# dynavo-amp.net
KiCad netlist of a schematic drawn in EAGLE
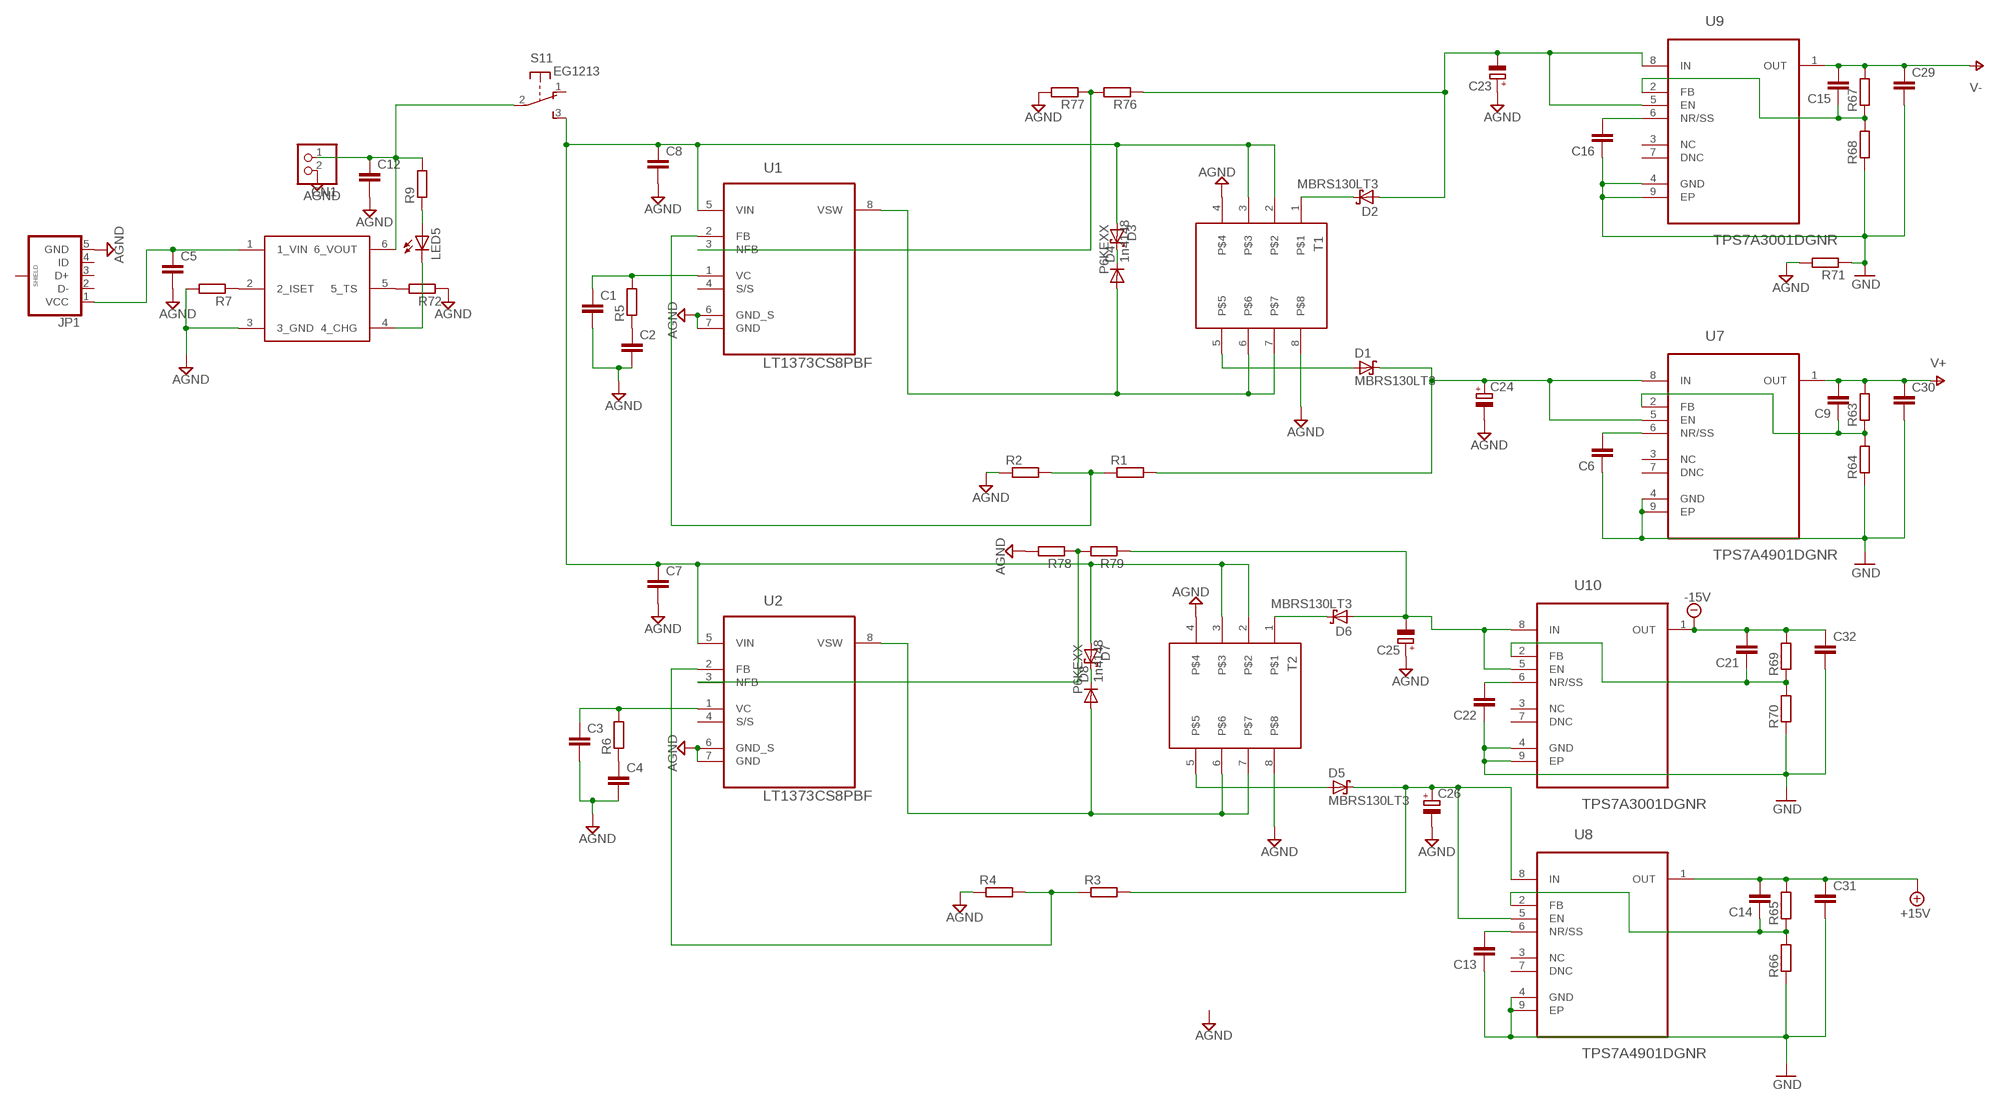
[diagram p0: schematic, sheet 1]
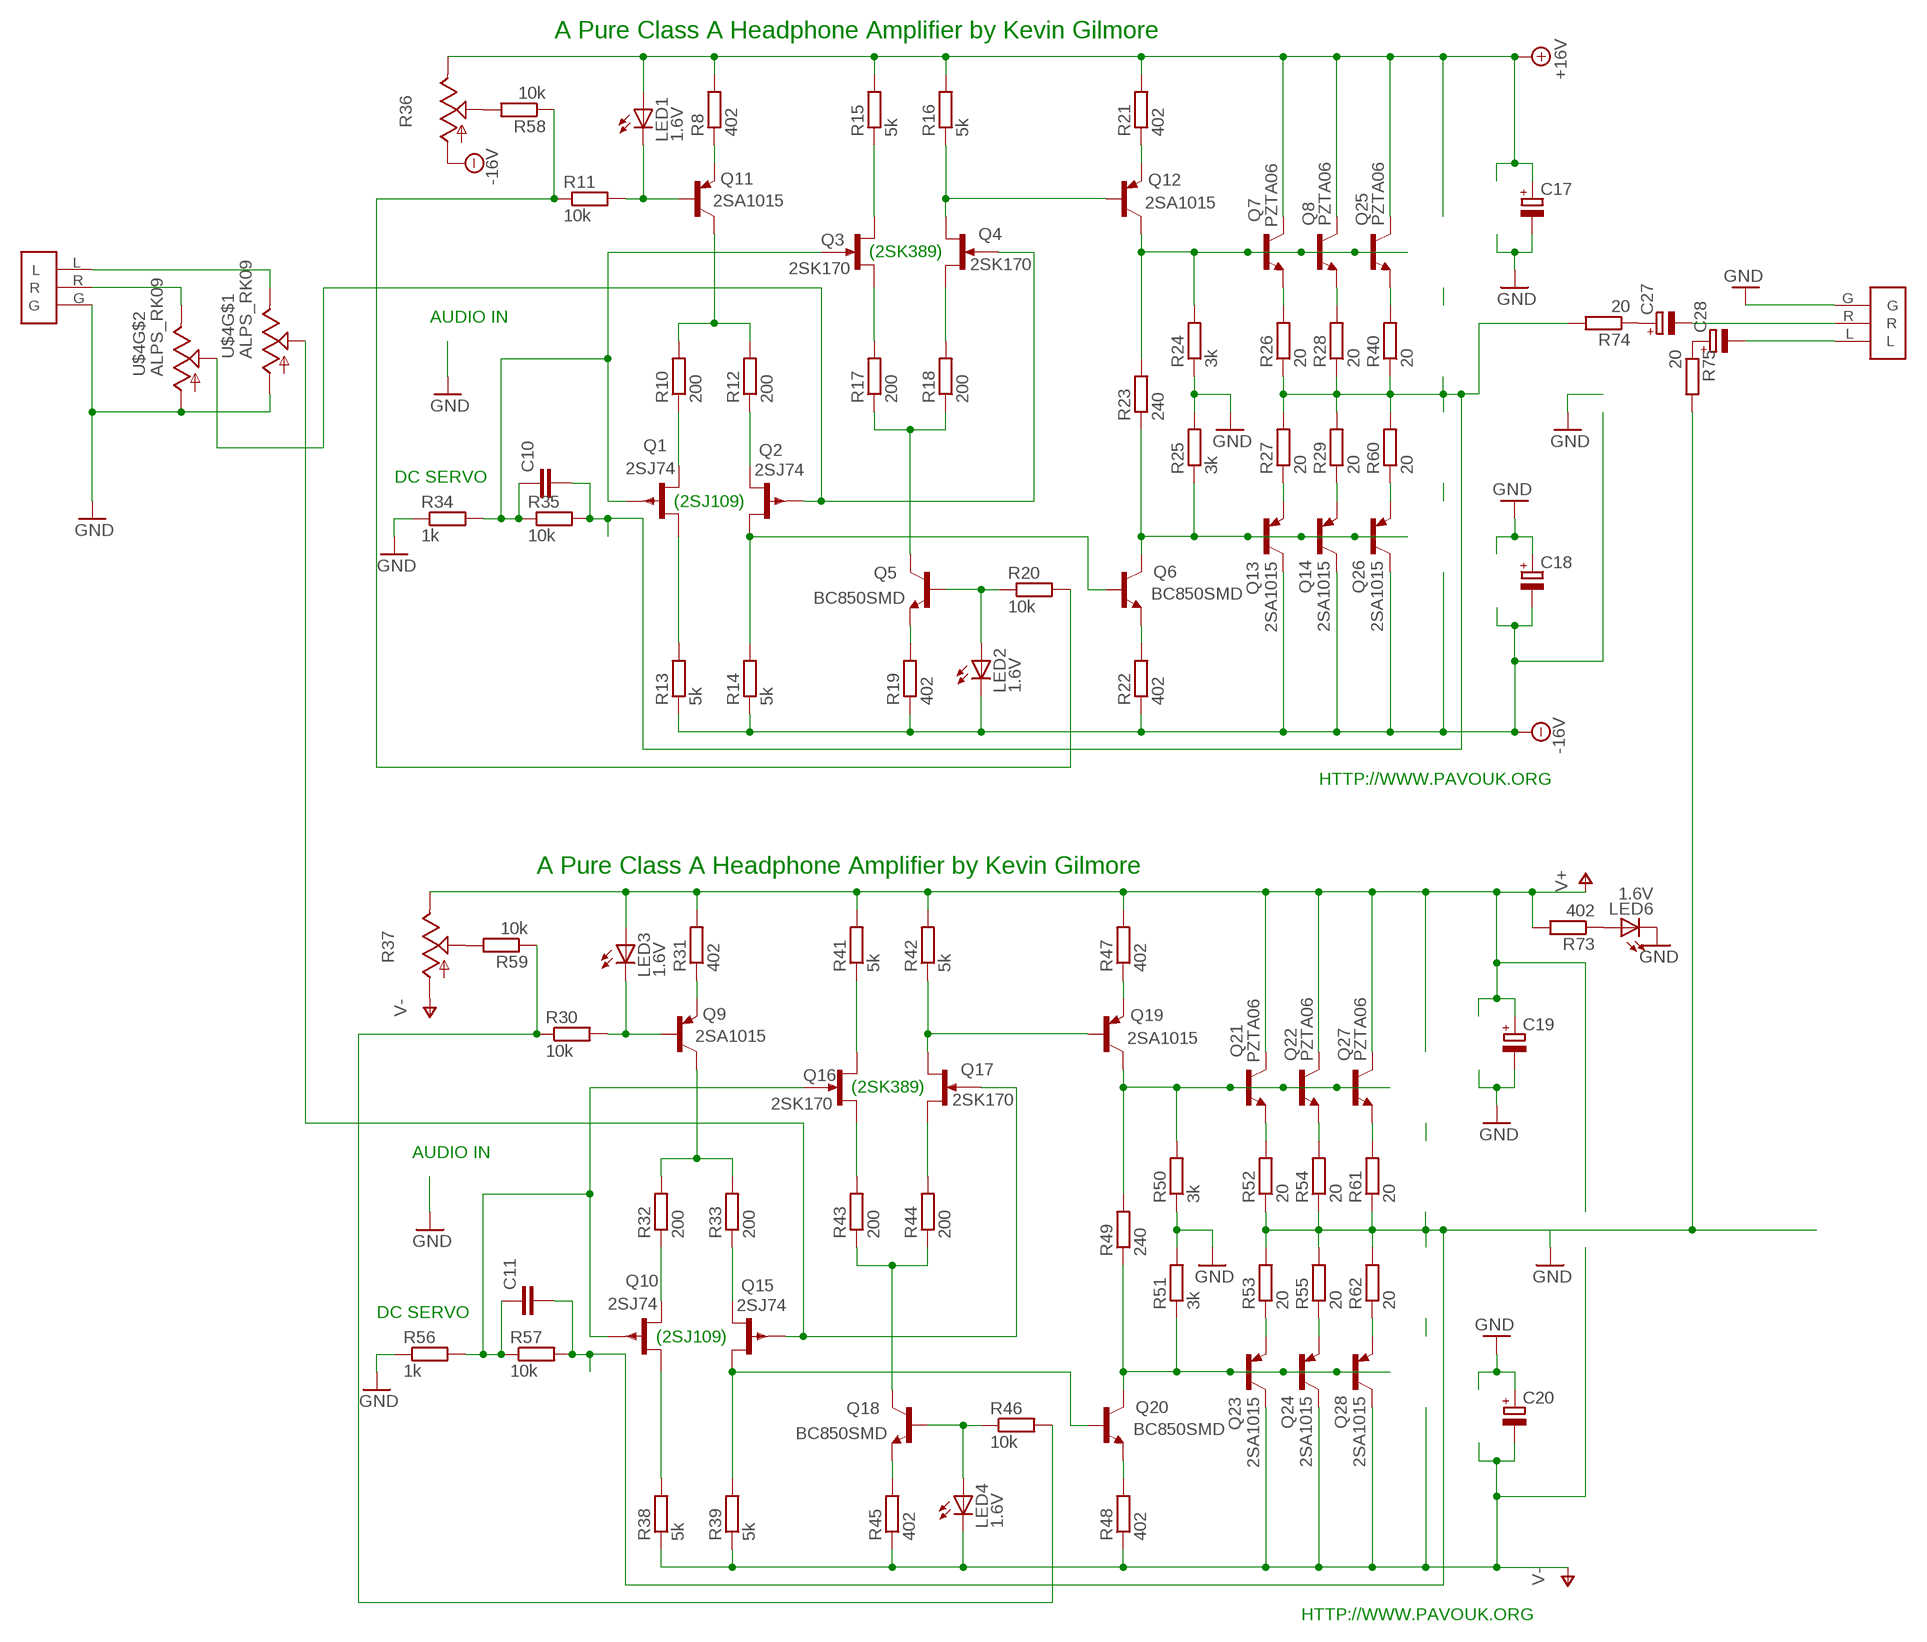
[diagram p1: schematic, sheet 2]

(export (version "E")
  (design (tool "Eeschema 10.0.6"))
  (components
    (comp (ref "C1")
      (value "C-EUC1210")
      (footprint "eagle-import:C1210")
      (libsource (lib "eagle-import") (part "C-EUC1210"))
    )
    (comp (ref "C2")
      (value "C-EUC1210")
      (footprint "eagle-import:C1210")
      (libsource (lib "eagle-import") (part "C-EUC1210"))
    )
    (comp (ref "C3")
      (value "C-EUC1210")
      (footprint "eagle-import:C1210")
      (libsource (lib "eagle-import") (part "C-EUC1210"))
    )
    (comp (ref "C4")
      (value "C-EUC1210")
      (footprint "eagle-import:C1210")
      (libsource (lib "eagle-import") (part "C-EUC1210"))
    )
    (comp (ref "C5")
      (value "C-EUC1210")
      (footprint "eagle-import:C1210")
      (libsource (lib "eagle-import") (part "C-EUC1210"))
    )
    (comp (ref "C6")
      (value "C-EUC1206")
      (footprint "eagle-import:C1206")
      (libsource (lib "eagle-import") (part "C-EUC1206"))
    )
    (comp (ref "C7")
      (value "C-EUC1210")
      (footprint "eagle-import:C1210")
      (libsource (lib "eagle-import") (part "C-EUC1210"))
    )
    (comp (ref "C8")
      (value "C-EUC1210")
      (footprint "eagle-import:C1210")
      (libsource (lib "eagle-import") (part "C-EUC1210"))
    )
    (comp (ref "C9")
      (value "C-EUC1206")
      (footprint "eagle-import:C1206")
      (libsource (lib "eagle-import") (part "C-EUC1206"))
    )
    (comp (ref "C12")
      (value "C-EUC1210")
      (footprint "eagle-import:C1210")
      (libsource (lib "eagle-import") (part "C-EUC1210"))
    )
    (comp (ref "C13")
      (value "C-EUC1206")
      (footprint "eagle-import:C1206")
      (libsource (lib "eagle-import") (part "C-EUC1206"))
    )
    (comp (ref "C14")
      (value "C-EUC1206")
      (footprint "eagle-import:C1206")
      (libsource (lib "eagle-import") (part "C-EUC1206"))
    )
    (comp (ref "C15")
      (value "C-EUC1206")
      (footprint "eagle-import:C1206")
      (libsource (lib "eagle-import") (part "C-EUC1206"))
    )
    (comp (ref "C16")
      (value "C-EUC1206")
      (footprint "eagle-import:C1206")
      (libsource (lib "eagle-import") (part "C-EUC1206"))
    )
    (comp (ref "C21")
      (value "C-EUC1206")
      (footprint "eagle-import:C1206")
      (libsource (lib "eagle-import") (part "C-EUC1206"))
    )
    (comp (ref "C22")
      (value "C-EUC1206")
      (footprint "eagle-import:C1206")
      (libsource (lib "eagle-import") (part "C-EUC1206"))
    )
    (comp (ref "C23")
      (value "CPOL-EUD/7343-31W")
      (footprint "eagle-import:D_7343-31W")
      (libsource (lib "eagle-import") (part "CPOL-EUD/7343-31W"))
    )
    (comp (ref "C24")
      (value "CPOL-EUD/7343-31W")
      (footprint "eagle-import:D_7343-31W")
      (libsource (lib "eagle-import") (part "CPOL-EUD/7343-31W"))
    )
    (comp (ref "C25")
      (value "CPOL-EUD/7343-31W")
      (footprint "eagle-import:D_7343-31W")
      (libsource (lib "eagle-import") (part "CPOL-EUD/7343-31W"))
    )
    (comp (ref "C26")
      (value "CPOL-EUD/7343-31W")
      (footprint "eagle-import:D_7343-31W")
      (libsource (lib "eagle-import") (part "CPOL-EUD/7343-31W"))
    )
    (comp (ref "C29")
      (value "C-EUC1206")
      (footprint "eagle-import:C1206")
      (libsource (lib "eagle-import") (part "C-EUC1206"))
    )
    (comp (ref "C30")
      (value "C-EUC1206")
      (footprint "eagle-import:C1206")
      (libsource (lib "eagle-import") (part "C-EUC1206"))
    )
    (comp (ref "C31")
      (value "C-EUC1206")
      (footprint "eagle-import:C1206")
      (libsource (lib "eagle-import") (part "C-EUC1206"))
    )
    (comp (ref "C32")
      (value "C-EUC1206")
      (footprint "eagle-import:C1206")
      (libsource (lib "eagle-import") (part "C-EUC1206"))
    )
    (comp (ref "CN1")
      (value "JST_2PIN-THM")
      (footprint "eagle-import:JST-PH-2-THM")
      (libsource (lib "eagle-import") (part "JST_2PIN-THM"))
    )
    (comp (ref "D1")
      (value "MBRS130LT3")
      (footprint "eagle-import:SMB")
      (libsource (lib "eagle-import") (part "MBRS130LT3"))
    )
    (comp (ref "D2")
      (value "MBRS130LT3")
      (footprint "eagle-import:SMB")
      (libsource (lib "eagle-import") (part "MBRS130LT3"))
    )
    (comp (ref "D3")
      (value "P6KEXX")
      (footprint "eagle-import:SMBJ")
      (libsource (lib "eagle-import") (part "P6KEXX"))
    )
    (comp (ref "D4")
      (value "1n4148")
      (footprint "eagle-import:SOD80C")
      (libsource (lib "eagle-import") (part "DIODE-SOD80C"))
    )
    (comp (ref "D5")
      (value "MBRS130LT3")
      (footprint "eagle-import:SMB")
      (libsource (lib "eagle-import") (part "MBRS130LT3"))
    )
    (comp (ref "D6")
      (value "MBRS130LT3")
      (footprint "eagle-import:SMB")
      (libsource (lib "eagle-import") (part "MBRS130LT3"))
    )
    (comp (ref "D7")
      (value "P6KEXX")
      (footprint "eagle-import:SMBJ")
      (libsource (lib "eagle-import") (part "P6KEXX"))
    )
    (comp (ref "D8")
      (value "1n4148")
      (footprint "eagle-import:SOD80C")
      (libsource (lib "eagle-import") (part "DIODE-SOD80C"))
    )
    (comp (ref "JP1")
      (value "USB_MICROB_PLUG-SMT")
      (footprint "eagle-import:MICRO-B-SMT")
      (libsource (lib "eagle-import") (part "USB_MICROB_PLUG-SMT"))
    )
    (comp (ref "LED5")
      (value "LED3MM")
      (footprint "eagle-import:LED3MM")
      (libsource (lib "eagle-import") (part "LED3MM"))
    )
    (comp (ref "R1")
      (value "R-EU_MELF0204W")
      (footprint "eagle-import:MINI_MELF-0204W")
      (libsource (lib "eagle-import") (part "R-EU_MELF0204W"))
    )
    (comp (ref "R2")
      (value "R-EU_MELF0204W")
      (footprint "eagle-import:MINI_MELF-0204W")
      (libsource (lib "eagle-import") (part "R-EU_MELF0204W"))
    )
    (comp (ref "R3")
      (value "R-EU_MELF0204W")
      (footprint "eagle-import:MINI_MELF-0204W")
      (libsource (lib "eagle-import") (part "R-EU_MELF0204W"))
    )
    (comp (ref "R4")
      (value "R-EU_MELF0204W")
      (footprint "eagle-import:MINI_MELF-0204W")
      (libsource (lib "eagle-import") (part "R-EU_MELF0204W"))
    )
    (comp (ref "R5")
      (value "R-EU_MELF0204W")
      (footprint "eagle-import:MINI_MELF-0204W")
      (libsource (lib "eagle-import") (part "R-EU_MELF0204W"))
    )
    (comp (ref "R6")
      (value "R-EU_MELF0204W")
      (footprint "eagle-import:MINI_MELF-0204W")
      (libsource (lib "eagle-import") (part "R-EU_MELF0204W"))
    )
    (comp (ref "R7")
      (value "R-EU_MELF0204W")
      (footprint "eagle-import:MINI_MELF-0204W")
      (libsource (lib "eagle-import") (part "R-EU_MELF0204W"))
    )
    (comp (ref "R9")
      (value "R-EU_MELF0204W")
      (footprint "eagle-import:MINI_MELF-0204W")
      (libsource (lib "eagle-import") (part "R-EU_MELF0204W"))
    )
    (comp (ref "R63")
      (value "R-EU_MELF0204W")
      (footprint "eagle-import:MINI_MELF-0204W")
      (libsource (lib "eagle-import") (part "R-EU_MELF0204W"))
    )
    (comp (ref "R64")
      (value "R-EU_MELF0204W")
      (footprint "eagle-import:MINI_MELF-0204W")
      (libsource (lib "eagle-import") (part "R-EU_MELF0204W"))
    )
    (comp (ref "R65")
      (value "R-EU_MELF0204W")
      (footprint "eagle-import:MINI_MELF-0204W")
      (libsource (lib "eagle-import") (part "R-EU_MELF0204W"))
    )
    (comp (ref "R66")
      (value "R-EU_MELF0204W")
      (footprint "eagle-import:MINI_MELF-0204W")
      (libsource (lib "eagle-import") (part "R-EU_MELF0204W"))
    )
    (comp (ref "R67")
      (value "R-EU_MELF0204W")
      (footprint "eagle-import:MINI_MELF-0204W")
      (libsource (lib "eagle-import") (part "R-EU_MELF0204W"))
    )
    (comp (ref "R68")
      (value "R-EU_MELF0204W")
      (footprint "eagle-import:MINI_MELF-0204W")
      (libsource (lib "eagle-import") (part "R-EU_MELF0204W"))
    )
    (comp (ref "R69")
      (value "R-EU_MELF0204W")
      (footprint "eagle-import:MINI_MELF-0204W")
      (libsource (lib "eagle-import") (part "R-EU_MELF0204W"))
    )
    (comp (ref "R70")
      (value "R-EU_MELF0204W")
      (footprint "eagle-import:MINI_MELF-0204W")
      (libsource (lib "eagle-import") (part "R-EU_MELF0204W"))
    )
    (comp (ref "R71")
      (value "R-EU_MELF0204W")
      (footprint "eagle-import:MINI_MELF-0204W")
      (libsource (lib "eagle-import") (part "R-EU_MELF0204W"))
    )
    (comp (ref "R72")
      (value "R-EU_MELF0204W")
      (footprint "eagle-import:MINI_MELF-0204W")
      (libsource (lib "eagle-import") (part "R-EU_MELF0204W"))
    )
    (comp (ref "R76")
      (value "R-EU_MELF0204W")
      (footprint "eagle-import:MINI_MELF-0204W")
      (libsource (lib "eagle-import") (part "R-EU_MELF0204W"))
    )
    (comp (ref "R77")
      (value "R-EU_MELF0204W")
      (footprint "eagle-import:MINI_MELF-0204W")
      (libsource (lib "eagle-import") (part "R-EU_MELF0204W"))
    )
    (comp (ref "R78")
      (value "R-EU_MELF0204W")
      (footprint "eagle-import:MINI_MELF-0204W")
      (libsource (lib "eagle-import") (part "R-EU_MELF0204W"))
    )
    (comp (ref "R79")
      (value "R-EU_MELF0204W")
      (footprint "eagle-import:MINI_MELF-0204W")
      (libsource (lib "eagle-import") (part "R-EU_MELF0204W"))
    )
    (comp (ref "S1")
      (value "EG1213")
      (footprint "eagle-import:EG1213")
      (libsource (lib "eagle-import") (part "EG1213"))
    )
    (comp (ref "T1")
      (value "LPE4841")
      (footprint "eagle-import:LPE4841")
      (libsource (lib "eagle-import") (part "LPE4841"))
    )
    (comp (ref "T2")
      (value "LPE4841")
      (footprint "eagle-import:LPE4841")
      (libsource (lib "eagle-import") (part "LPE4841"))
    )
    (comp (ref "U1")
      (value "LT1373CS8PBF")
      (footprint "eagle-import:SOIC127P600X175-8N")
      (fields (field (name "MPN") "LT1373CS8#PBF"))
      (libsource (lib "eagle-import") (part "LT1373CS8PBF"))
    )
    (comp (ref "U2")
      (value "LT1373CS8PBF")
      (footprint "eagle-import:SOIC127P600X175-8N")
      (fields (field (name "MPN") "LT1373CS8#PBF"))
      (libsource (lib "eagle-import") (part "LT1373CS8PBF"))
    )
    (comp (ref "U3")
      (value "BQ21040")
      (footprint "eagle-import:SOT-23-6")
      (libsource (lib "eagle-import") (part "BQ21040"))
    )
    (comp (ref "U7")
      (value "TPS7A4901DGNR")
      (footprint "eagle-import:SOP65P490X110-9N")
      (libsource (lib "eagle-import") (part "TPS7A4901DGNR"))
    )
    (comp (ref "U8")
      (value "TPS7A4901DGNR")
      (footprint "eagle-import:SOP65P490X110-9N")
      (libsource (lib "eagle-import") (part "TPS7A4901DGNR"))
    )
    (comp (ref "U9")
      (value "TPS7A3001DGNR")
      (footprint "eagle-import:SOP65P490X110-9N")
      (libsource (lib "eagle-import") (part "TPS7A3001DGNR"))
    )
    (comp (ref "U10")
      (value "TPS7A3001DGNR")
      (footprint "eagle-import:SOP65P490X110-9N")
      (libsource (lib "eagle-import") (part "TPS7A3001DGNR"))
    )
    (comp (ref "C10")
      (value "C-EUC1206")
      (footprint "eagle-import:C1206")
      (libsource (lib "eagle-import") (part "C-EUC1206"))
    )
    (comp (ref "C11")
      (value "C-EUC1206")
      (footprint "eagle-import:C1206")
      (libsource (lib "eagle-import") (part "C-EUC1206"))
    )
    (comp (ref "C17")
      (value "CPOL-EUD/7343-31W")
      (footprint "eagle-import:D_7343-31W")
      (libsource (lib "eagle-import") (part "CPOL-EUD/7343-31W"))
    )
    (comp (ref "C18")
      (value "CPOL-EUD/7343-31W")
      (footprint "eagle-import:D_7343-31W")
      (libsource (lib "eagle-import") (part "CPOL-EUD/7343-31W"))
    )
    (comp (ref "C19")
      (value "CPOL-EUD/7343-31W")
      (footprint "eagle-import:D_7343-31W")
      (libsource (lib "eagle-import") (part "CPOL-EUD/7343-31W"))
    )
    (comp (ref "C20")
      (value "CPOL-EUD/7343-31W")
      (footprint "eagle-import:D_7343-31W")
      (libsource (lib "eagle-import") (part "CPOL-EUD/7343-31W"))
    )
    (comp (ref "C27")
      (value "CPOL-EUD/7343-31W")
      (footprint "eagle-import:D_7343-31W")
      (libsource (lib "eagle-import") (part "CPOL-EUD/7343-31W"))
    )
    (comp (ref "C28")
      (value "CPOL-EUD/7343-31W")
      (footprint "eagle-import:D_7343-31W")
      (libsource (lib "eagle-import") (part "CPOL-EUD/7343-31W"))
    )
    (comp (ref "LED1")
      (value "1.6V")
      (footprint "eagle-import:CHIPLED_1206")
      (libsource (lib "eagle-import") (part "LEDCHIPLED_1206"))
    )
    (comp (ref "LED2")
      (value "1.6V")
      (footprint "eagle-import:CHIPLED_1206")
      (libsource (lib "eagle-import") (part "LEDCHIPLED_1206"))
    )
    (comp (ref "LED3")
      (value "1.6V")
      (footprint "eagle-import:CHIPLED_1206")
      (libsource (lib "eagle-import") (part "LEDCHIPLED_1206"))
    )
    (comp (ref "LED4")
      (value "1.6V")
      (footprint "eagle-import:CHIPLED_1206")
      (libsource (lib "eagle-import") (part "LEDCHIPLED_1206"))
    )
    (comp (ref "LED6")
      (value "1.6V")
      (footprint "eagle-import:CHIPLED_1206")
      (libsource (lib "eagle-import") (part "LEDCHIPLED_1206"))
    )
    (comp (ref "Q1")
      (value "2SJ74")
      (footprint "eagle-import:SOT23")
      (libsource (lib "eagle-import") (part "MMBF5462"))
    )
    (comp (ref "Q2")
      (value "2SJ74")
      (footprint "eagle-import:SOT23")
      (libsource (lib "eagle-import") (part "MMBF5462"))
    )
    (comp (ref "Q3")
      (value "2SK170")
      (footprint "eagle-import:SOT23")
      (libsource (lib "eagle-import") (part "MMBFJ202"))
    )
    (comp (ref "Q4")
      (value "2SK170")
      (footprint "eagle-import:SOT23")
      (libsource (lib "eagle-import") (part "MMBFJ202"))
    )
    (comp (ref "Q5")
      (value "BC850SMD")
      (footprint "eagle-import:SOT23-BEC")
      (libsource (lib "eagle-import") (part "BC850SMD"))
    )
    (comp (ref "Q6")
      (value "BC850SMD")
      (footprint "eagle-import:SOT23-BEC")
      (libsource (lib "eagle-import") (part "BC850SMD"))
    )
    (comp (ref "Q7")
      (value "PZTA06")
      (footprint "eagle-import:SOT223R_INFINEON")
      (libsource (lib "eagle-import") (part "PZTA06"))
    )
    (comp (ref "Q8")
      (value "PZTA06")
      (footprint "eagle-import:SOT223R_INFINEON")
      (libsource (lib "eagle-import") (part "PZTA06"))
    )
    (comp (ref "Q9")
      (value "2SA1015")
      (footprint "eagle-import:SOT23-BEC")
      (libsource (lib "eagle-import") (part "BC860SMDC"))
    )
    (comp (ref "Q10")
      (value "2SJ74")
      (footprint "eagle-import:SOT23")
      (libsource (lib "eagle-import") (part "MMBF5462"))
    )
    (comp (ref "Q11")
      (value "2SA1015")
      (footprint "eagle-import:SOT23-BEC")
      (libsource (lib "eagle-import") (part "BC860SMDC"))
    )
    (comp (ref "Q12")
      (value "2SA1015")
      (footprint "eagle-import:SOT23-BEC")
      (libsource (lib "eagle-import") (part "BC860SMDC"))
    )
    (comp (ref "Q13")
      (value "2SA1015")
      (footprint "eagle-import:SOT223R_INFINEON")
      (libsource (lib "eagle-import") (part "PZTA56"))
    )
    (comp (ref "Q14")
      (value "2SA1015")
      (footprint "eagle-import:SOT223R_INFINEON")
      (libsource (lib "eagle-import") (part "PZTA56"))
    )
    (comp (ref "Q15")
      (value "2SJ74")
      (footprint "eagle-import:SOT23")
      (libsource (lib "eagle-import") (part "MMBF5462"))
    )
    (comp (ref "Q16")
      (value "2SK170")
      (footprint "eagle-import:SOT23")
      (libsource (lib "eagle-import") (part "MMBFJ202"))
    )
    (comp (ref "Q17")
      (value "2SK170")
      (footprint "eagle-import:SOT23")
      (libsource (lib "eagle-import") (part "MMBFJ202"))
    )
    (comp (ref "Q18")
      (value "BC850SMD")
      (footprint "eagle-import:SOT23-BEC")
      (libsource (lib "eagle-import") (part "BC850SMD"))
    )
    (comp (ref "Q19")
      (value "2SA1015")
      (footprint "eagle-import:SOT23-BEC")
      (libsource (lib "eagle-import") (part "BC860SMDC"))
    )
    (comp (ref "Q20")
      (value "BC850SMD")
      (footprint "eagle-import:SOT23-BEC")
      (libsource (lib "eagle-import") (part "BC850SMD"))
    )
    (comp (ref "Q21")
      (value "PZTA06")
      (footprint "eagle-import:SOT223R_INFINEON")
      (libsource (lib "eagle-import") (part "PZTA06"))
    )
    (comp (ref "Q22")
      (value "PZTA06")
      (footprint "eagle-import:SOT223R_INFINEON")
      (libsource (lib "eagle-import") (part "PZTA06"))
    )
    (comp (ref "Q23")
      (value "2SA1015")
      (footprint "eagle-import:SOT223R_INFINEON")
      (libsource (lib "eagle-import") (part "PZTA56"))
    )
    (comp (ref "Q24")
      (value "2SA1015")
      (footprint "eagle-import:SOT223R_INFINEON")
      (libsource (lib "eagle-import") (part "PZTA56"))
    )
    (comp (ref "Q25")
      (value "PZTA06")
      (footprint "eagle-import:SOT223R_INFINEON")
      (libsource (lib "eagle-import") (part "PZTA06"))
    )
    (comp (ref "Q26")
      (value "2SA1015")
      (footprint "eagle-import:SOT223R_INFINEON")
      (libsource (lib "eagle-import") (part "PZTA56"))
    )
    (comp (ref "Q27")
      (value "PZTA06")
      (footprint "eagle-import:SOT223R_INFINEON")
      (libsource (lib "eagle-import") (part "PZTA06"))
    )
    (comp (ref "Q28")
      (value "2SA1015")
      (footprint "eagle-import:SOT223R_INFINEON")
      (libsource (lib "eagle-import") (part "PZTA56"))
    )
    (comp (ref "R8")
      (value "402")
      (footprint "eagle-import:MINI_MELF-0204W")
      (libsource (lib "eagle-import") (part "R-EU_MELF0204W"))
    )
    (comp (ref "R10")
      (value "200")
      (footprint "eagle-import:MINI_MELF-0204W")
      (libsource (lib "eagle-import") (part "R-EU_MELF0204W"))
    )
    (comp (ref "R11")
      (value "10k")
      (footprint "eagle-import:MINI_MELF-0204W")
      (libsource (lib "eagle-import") (part "R-EU_MELF0204W"))
    )
    (comp (ref "R12")
      (value "200")
      (footprint "eagle-import:MINI_MELF-0204W")
      (libsource (lib "eagle-import") (part "R-EU_MELF0204W"))
    )
    (comp (ref "R13")
      (value "5k")
      (footprint "eagle-import:MINI_MELF-0204W")
      (libsource (lib "eagle-import") (part "R-EU_MELF0204W"))
    )
    (comp (ref "R14")
      (value "5k")
      (footprint "eagle-import:MINI_MELF-0204W")
      (libsource (lib "eagle-import") (part "R-EU_MELF0204W"))
    )
    (comp (ref "R15")
      (value "5k")
      (footprint "eagle-import:MINI_MELF-0204W")
      (libsource (lib "eagle-import") (part "R-EU_MELF0204W"))
    )
    (comp (ref "R16")
      (value "5k")
      (footprint "eagle-import:MINI_MELF-0204W")
      (libsource (lib "eagle-import") (part "R-EU_MELF0204W"))
    )
    (comp (ref "R17")
      (value "200")
      (footprint "eagle-import:MINI_MELF-0204W")
      (libsource (lib "eagle-import") (part "R-EU_MELF0204W"))
    )
    (comp (ref "R18")
      (value "200")
      (footprint "eagle-import:MINI_MELF-0204W")
      (libsource (lib "eagle-import") (part "R-EU_MELF0204W"))
    )
    (comp (ref "R19")
      (value "402")
      (footprint "eagle-import:MINI_MELF-0204W")
      (libsource (lib "eagle-import") (part "R-EU_MELF0204W"))
    )
    (comp (ref "R20")
      (value "10k")
      (footprint "eagle-import:MINI_MELF-0204W")
      (libsource (lib "eagle-import") (part "R-EU_MELF0204W"))
    )
    (comp (ref "R21")
      (value "402")
      (footprint "eagle-import:MINI_MELF-0204W")
      (libsource (lib "eagle-import") (part "R-EU_MELF0204W"))
    )
    (comp (ref "R22")
      (value "402")
      (footprint "eagle-import:MINI_MELF-0204W")
      (libsource (lib "eagle-import") (part "R-EU_MELF0204W"))
    )
    (comp (ref "R23")
      (value "240")
      (footprint "eagle-import:MINI_MELF-0204W")
      (libsource (lib "eagle-import") (part "R-EU_MELF0204W"))
    )
    (comp (ref "R24")
      (value "3k")
      (footprint "eagle-import:MINI_MELF-0204W")
      (libsource (lib "eagle-import") (part "R-EU_MELF0204W"))
    )
    (comp (ref "R25")
      (value "3k")
      (footprint "eagle-import:MINI_MELF-0204W")
      (libsource (lib "eagle-import") (part "R-EU_MELF0204W"))
    )
    (comp (ref "R26")
      (value "20")
      (footprint "eagle-import:MINI_MELF-0204W")
      (libsource (lib "eagle-import") (part "R-EU_MELF0204W"))
    )
    (comp (ref "R27")
      (value "20")
      (footprint "eagle-import:MINI_MELF-0204W")
      (libsource (lib "eagle-import") (part "R-EU_MELF0204W"))
    )
    (comp (ref "R28")
      (value "20")
      (footprint "eagle-import:MINI_MELF-0204W")
      (libsource (lib "eagle-import") (part "R-EU_MELF0204W"))
    )
    (comp (ref "R29")
      (value "20")
      (footprint "eagle-import:MINI_MELF-0204W")
      (libsource (lib "eagle-import") (part "R-EU_MELF0204W"))
    )
    (comp (ref "R30")
      (value "10k")
      (footprint "eagle-import:MINI_MELF-0204W")
      (libsource (lib "eagle-import") (part "R-EU_MELF0204W"))
    )
    (comp (ref "R31")
      (value "402")
      (footprint "eagle-import:MINI_MELF-0204W")
      (libsource (lib "eagle-import") (part "R-EU_MELF0204W"))
    )
    (comp (ref "R32")
      (value "200")
      (footprint "eagle-import:MINI_MELF-0204W")
      (libsource (lib "eagle-import") (part "R-EU_MELF0204W"))
    )
    (comp (ref "R33")
      (value "200")
      (footprint "eagle-import:MINI_MELF-0204W")
      (libsource (lib "eagle-import") (part "R-EU_MELF0204W"))
    )
    (comp (ref "R34")
      (value "1k")
      (footprint "eagle-import:MINI_MELF-0204W")
      (libsource (lib "eagle-import") (part "R-EU_MELF0204W"))
    )
    (comp (ref "R35")
      (value "10k")
      (footprint "eagle-import:MINI_MELF-0204W")
      (libsource (lib "eagle-import") (part "R-EU_MELF0204W"))
    )
    (comp (ref "R36")
      (value "TRIM_US-3223G")
      (footprint "eagle-import:3223G")
      (libsource (lib "eagle-import") (part "TRIM_US-3223G"))
    )
    (comp (ref "R37")
      (value "TRIM_US-3223G")
      (footprint "eagle-import:3223G")
      (libsource (lib "eagle-import") (part "TRIM_US-3223G"))
    )
    (comp (ref "R38")
      (value "5k")
      (footprint "eagle-import:MINI_MELF-0204W")
      (libsource (lib "eagle-import") (part "R-EU_MELF0204W"))
    )
    (comp (ref "R39")
      (value "5k")
      (footprint "eagle-import:MINI_MELF-0204W")
      (libsource (lib "eagle-import") (part "R-EU_MELF0204W"))
    )
    (comp (ref "R40")
      (value "20")
      (footprint "eagle-import:MINI_MELF-0204W")
      (libsource (lib "eagle-import") (part "R-EU_MELF0204W"))
    )
    (comp (ref "R41")
      (value "5k")
      (footprint "eagle-import:MINI_MELF-0204W")
      (libsource (lib "eagle-import") (part "R-EU_MELF0204W"))
    )
    (comp (ref "R42")
      (value "5k")
      (footprint "eagle-import:MINI_MELF-0204W")
      (libsource (lib "eagle-import") (part "R-EU_MELF0204W"))
    )
    (comp (ref "R43")
      (value "200")
      (footprint "eagle-import:MINI_MELF-0204W")
      (libsource (lib "eagle-import") (part "R-EU_MELF0204W"))
    )
    (comp (ref "R44")
      (value "200")
      (footprint "eagle-import:MINI_MELF-0204W")
      (libsource (lib "eagle-import") (part "R-EU_MELF0204W"))
    )
    (comp (ref "R45")
      (value "402")
      (footprint "eagle-import:MINI_MELF-0204W")
      (libsource (lib "eagle-import") (part "R-EU_MELF0204W"))
    )
    (comp (ref "R46")
      (value "10k")
      (footprint "eagle-import:MINI_MELF-0204W")
      (libsource (lib "eagle-import") (part "R-EU_MELF0204W"))
    )
    (comp (ref "R47")
      (value "402")
      (footprint "eagle-import:MINI_MELF-0204W")
      (libsource (lib "eagle-import") (part "R-EU_MELF0204W"))
    )
    (comp (ref "R48")
      (value "402")
      (footprint "eagle-import:MINI_MELF-0204W")
      (libsource (lib "eagle-import") (part "R-EU_MELF0204W"))
    )
    (comp (ref "R49")
      (value "240")
      (footprint "eagle-import:MINI_MELF-0204W")
      (libsource (lib "eagle-import") (part "R-EU_MELF0204W"))
    )
    (comp (ref "R50")
      (value "3k")
      (footprint "eagle-import:MINI_MELF-0204W")
      (libsource (lib "eagle-import") (part "R-EU_MELF0204W"))
    )
    (comp (ref "R51")
      (value "3k")
      (footprint "eagle-import:MINI_MELF-0204W")
      (libsource (lib "eagle-import") (part "R-EU_MELF0204W"))
    )
    (comp (ref "R52")
      (value "20")
      (footprint "eagle-import:MINI_MELF-0204W")
      (libsource (lib "eagle-import") (part "R-EU_MELF0204W"))
    )
    (comp (ref "R53")
      (value "20")
      (footprint "eagle-import:MINI_MELF-0204W")
      (libsource (lib "eagle-import") (part "R-EU_MELF0204W"))
    )
    (comp (ref "R54")
      (value "20")
      (footprint "eagle-import:MINI_MELF-0204W")
      (libsource (lib "eagle-import") (part "R-EU_MELF0204W"))
    )
    (comp (ref "R55")
      (value "20")
      (footprint "eagle-import:MINI_MELF-0204W")
      (libsource (lib "eagle-import") (part "R-EU_MELF0204W"))
    )
    (comp (ref "R56")
      (value "1k")
      (footprint "eagle-import:MINI_MELF-0204W")
      (libsource (lib "eagle-import") (part "R-EU_MELF0204W"))
    )
    (comp (ref "R57")
      (value "10k")
      (footprint "eagle-import:MINI_MELF-0204W")
      (libsource (lib "eagle-import") (part "R-EU_MELF0204W"))
    )
    (comp (ref "R58")
      (value "10k")
      (footprint "eagle-import:MINI_MELF-0204W")
      (libsource (lib "eagle-import") (part "R-EU_MELF0204W"))
    )
    (comp (ref "R59")
      (value "10k")
      (footprint "eagle-import:MINI_MELF-0204W")
      (libsource (lib "eagle-import") (part "R-EU_MELF0204W"))
    )
    (comp (ref "R60")
      (value "20")
      (footprint "eagle-import:MINI_MELF-0204W")
      (libsource (lib "eagle-import") (part "R-EU_MELF0204W"))
    )
    (comp (ref "R61")
      (value "20")
      (footprint "eagle-import:MINI_MELF-0204W")
      (libsource (lib "eagle-import") (part "R-EU_MELF0204W"))
    )
    (comp (ref "R62")
      (value "20")
      (footprint "eagle-import:MINI_MELF-0204W")
      (libsource (lib "eagle-import") (part "R-EU_MELF0204W"))
    )
    (comp (ref "R73")
      (value "402")
      (footprint "eagle-import:MINI_MELF-0204W")
      (libsource (lib "eagle-import") (part "R-EU_MELF0204W"))
    )
    (comp (ref "R74")
      (value "20")
      (footprint "eagle-import:MINI_MELF-0204W")
      (libsource (lib "eagle-import") (part "R-EU_MELF0204W"))
    )
    (comp (ref "R75")
      (value "20")
      (footprint "eagle-import:MINI_MELF-0204W")
      (libsource (lib "eagle-import") (part "R-EU_MELF0204W"))
    )
    (comp (ref "U$2")
      (value "HPJACK")
      (footprint "eagle-import:FOXCON-PHONEJACK")
      (libsource (lib "eagle-import") (part "HPJACK"))
    )
    (comp (ref "U$3")
      (value "HPJACK")
      (footprint "eagle-import:FOXCON-PHONEJACK")
      (libsource (lib "eagle-import") (part "HPJACK"))
    )
    (comp (ref "U$4")
      (value "ALPS_RK09")
      (footprint "eagle-import:RK09")
      (libsource (lib "eagle-import") (part "ALPS_RK09"))
    )
  )
  (nets
    (net (code "1") (name "+15V") (class "Default")
      (node (ref "C14") (pin "2") (pinfunction "2_2") (pintype "passive"))
      (node (ref "C17") (pin "+") (pinfunction "+_+") (pintype "passive"))
      (node (ref "C31") (pin "1") (pinfunction "1_1") (pintype "passive"))
      (node (ref "LED1") (pin "A") (pinfunction "A_A") (pintype "passive"))
      (node (ref "Q25") (pin "2") (pinfunction "C_2") (pintype "passive"))
      (node (ref "Q25") (pin "4") (pinfunction "C_4") (pintype "passive"))
      (node (ref "Q7") (pin "2") (pinfunction "C_2") (pintype "passive"))
      (node (ref "Q7") (pin "4") (pinfunction "C_4") (pintype "passive"))
      (node (ref "Q8") (pin "2") (pinfunction "C_2") (pintype "passive"))
      (node (ref "Q8") (pin "4") (pinfunction "C_4") (pintype "passive"))
      (node (ref "R15") (pin "2") (pinfunction "2_2") (pintype "passive"))
      (node (ref "R16") (pin "2") (pinfunction "2_2") (pintype "passive"))
      (node (ref "R21") (pin "2") (pinfunction "2_2") (pintype "passive"))
      (node (ref "R36") (pin "3") (pinfunction "E_3") (pintype "passive"))
      (node (ref "R65") (pin "2") (pinfunction "2_2") (pintype "passive"))
      (node (ref "R8") (pin "2") (pinfunction "2_2") (pintype "passive"))
      (node (ref "U8") (pin "1") (pinfunction "OUT_1") (pintype "output"))
    )
    (net (code "2") (name "-15V") (class "Default")
      (node (ref "C18") (pin "-") (pinfunction "-_-") (pintype "passive"))
      (node (ref "C21") (pin "2") (pinfunction "2_2") (pintype "passive"))
      (node (ref "C32") (pin "1") (pinfunction "1_1") (pintype "passive"))
      (node (ref "LED2") (pin "C") (pinfunction "C_C") (pintype "passive"))
      (node (ref "Q13") (pin "2") (pinfunction "C_2") (pintype "passive"))
      (node (ref "Q13") (pin "4") (pinfunction "C_4") (pintype "passive"))
      (node (ref "Q14") (pin "2") (pinfunction "C_2") (pintype "passive"))
      (node (ref "Q14") (pin "4") (pinfunction "C_4") (pintype "passive"))
      (node (ref "Q26") (pin "2") (pinfunction "C_2") (pintype "passive"))
      (node (ref "Q26") (pin "4") (pinfunction "C_4") (pintype "passive"))
      (node (ref "R13") (pin "1") (pinfunction "1_1") (pintype "passive"))
      (node (ref "R14") (pin "1") (pinfunction "1_1") (pintype "passive"))
      (node (ref "R19") (pin "1") (pinfunction "1_1") (pintype "passive"))
      (node (ref "R22") (pin "1") (pinfunction "1_1") (pintype "passive"))
      (node (ref "R36") (pin "1") (pinfunction "A_1") (pintype "passive"))
      (node (ref "R69") (pin "2") (pinfunction "2_2") (pintype "passive"))
      (node (ref "U10") (pin "1") (pinfunction "OUT_1") (pintype "output"))
    )
    (net (code "3") (name "AGND") (class "Default")
      (node (ref "C1") (pin "2") (pinfunction "2_2") (pintype "passive"))
      (node (ref "C12") (pin "2") (pinfunction "2_2") (pintype "passive"))
      (node (ref "C2") (pin "2") (pinfunction "2_2") (pintype "passive"))
      (node (ref "C23") (pin "+") (pinfunction "+_+") (pintype "passive"))
      (node (ref "C24") (pin "-") (pinfunction "-_-") (pintype "passive"))
      (node (ref "C25") (pin "+") (pinfunction "+_+") (pintype "passive"))
      (node (ref "C26") (pin "-") (pinfunction "-_-") (pintype "passive"))
      (node (ref "C3") (pin "2") (pinfunction "2_2") (pintype "passive"))
      (node (ref "C4") (pin "2") (pinfunction "2_2") (pintype "passive"))
      (node (ref "C5") (pin "2") (pinfunction "2_2") (pintype "passive"))
      (node (ref "C7") (pin "2") (pinfunction "2_2") (pintype "passive"))
      (node (ref "C8") (pin "2") (pinfunction "2_2") (pintype "passive"))
      (node (ref "CN1") (pin "2") (pinfunction "1_2") (pintype "passive"))
      (node (ref "JP1") (pin "5") (pinfunction "GND_5") (pintype "bidirectional"))
      (node (ref "R2") (pin "1") (pinfunction "1_1") (pintype "passive"))
      (node (ref "R4") (pin "1") (pinfunction "1_1") (pintype "passive"))
      (node (ref "R7") (pin "2") (pinfunction "2_2") (pintype "passive"))
      (node (ref "R71") (pin "2") (pinfunction "2_2") (pintype "passive"))
      (node (ref "R72") (pin "1") (pinfunction "1_1") (pintype "passive"))
      (node (ref "R77") (pin "2") (pinfunction "2_2") (pintype "passive"))
      (node (ref "R78") (pin "2") (pinfunction "2_2") (pintype "passive"))
      (node (ref "T1") (pin "4") (pinfunction "P$4_4") (pintype "bidirectional"))
      (node (ref "T1") (pin "8") (pinfunction "P$8_8") (pintype "bidirectional"))
      (node (ref "T2") (pin "4") (pinfunction "P$4_4") (pintype "bidirectional"))
      (node (ref "T2") (pin "8") (pinfunction "P$8_8") (pintype "bidirectional"))
      (node (ref "U1") (pin "6") (pinfunction "GND_S_6") (pintype "passive"))
      (node (ref "U1") (pin "7") (pinfunction "GND_7") (pintype "passive"))
      (node (ref "U2") (pin "6") (pinfunction "GND_S_6") (pintype "passive"))
      (node (ref "U2") (pin "7") (pinfunction "GND_7") (pintype "passive"))
      (node (ref "U3") (pin "3") (pinfunction "3_GND_3") (pintype "bidirectional"))
    )
    (net (code "4") (name "GND") (class "Default")
      (node (ref "C13") (pin "1") (pinfunction "1_1") (pintype "passive"))
      (node (ref "C16") (pin "1") (pinfunction "1_1") (pintype "passive"))
      (node (ref "C17") (pin "-") (pinfunction "-_-") (pintype "passive"))
      (node (ref "C18") (pin "+") (pinfunction "+_+") (pintype "passive"))
      (node (ref "C19") (pin "-") (pinfunction "-_-") (pintype "passive"))
      (node (ref "C20") (pin "+") (pinfunction "+_+") (pintype "passive"))
      (node (ref "C22") (pin "1") (pinfunction "1_1") (pintype "passive"))
      (node (ref "C29") (pin "2") (pinfunction "2_2") (pintype "passive"))
      (node (ref "C30") (pin "2") (pinfunction "2_2") (pintype "passive"))
      (node (ref "C31") (pin "2") (pinfunction "2_2") (pintype "passive"))
      (node (ref "C32") (pin "2") (pinfunction "2_2") (pintype "passive"))
      (node (ref "C6") (pin "1") (pinfunction "1_1") (pintype "passive"))
      (node (ref "LED6") (pin "C") (pinfunction "C_C") (pintype "passive"))
      (node (ref "R24") (pin "1") (pinfunction "1_1") (pintype "passive"))
      (node (ref "R25") (pin "2") (pinfunction "2_2") (pintype "passive"))
      (node (ref "R34") (pin "1") (pinfunction "1_1") (pintype "passive"))
      (node (ref "R50") (pin "1") (pinfunction "1_1") (pintype "passive"))
      (node (ref "R51") (pin "2") (pinfunction "2_2") (pintype "passive"))
      (node (ref "R56") (pin "1") (pinfunction "1_1") (pintype "passive"))
      (node (ref "R64") (pin "1") (pinfunction "1_1") (pintype "passive"))
      (node (ref "R66") (pin "1") (pinfunction "1_1") (pintype "passive"))
      (node (ref "R68") (pin "1") (pinfunction "1_1") (pintype "passive"))
      (node (ref "R70") (pin "1") (pinfunction "1_1") (pintype "passive"))
      (node (ref "R71") (pin "1") (pinfunction "1_1") (pintype "passive"))
      (node (ref "U$2") (pin "G") (pinfunction "G_G") (pintype "bidirectional"))
      (node (ref "U$3") (pin "G") (pinfunction "G_G") (pintype "bidirectional"))
      (node (ref "U$4") (pin "G1") (pinfunction "1_G1") (pintype "passive"))
      (node (ref "U$4") (pin "G2") (pinfunction "1_G2") (pintype "passive"))
      (node (ref "U10") (pin "4") (pinfunction "GND_4") (pintype "passive"))
      (node (ref "U10") (pin "9") (pinfunction "EP_9") (pintype "passive"))
      (node (ref "U7") (pin "4") (pinfunction "GND_4") (pintype "passive"))
      (node (ref "U7") (pin "9") (pinfunction "EP_9") (pintype "passive"))
      (node (ref "U8") (pin "4") (pinfunction "GND_4") (pintype "passive"))
      (node (ref "U8") (pin "9") (pinfunction "EP_9") (pintype "passive"))
      (node (ref "U9") (pin "4") (pinfunction "GND_4") (pintype "passive"))
      (node (ref "U9") (pin "9") (pinfunction "EP_9") (pintype "passive"))
    )
    (net (code "5") (name "Net-(C2-Pad1)") (class "Default")
      (node (ref "C2") (pin "1") (pinfunction "1_1") (pintype "passive"))
      (node (ref "R5") (pin "1") (pinfunction "1_1") (pintype "passive"))
    )
    (net (code "6") (name "Net-(C4-Pad1)") (class "Default")
      (node (ref "C4") (pin "1") (pinfunction "1_1") (pintype "passive"))
      (node (ref "R6") (pin "1") (pinfunction "1_1") (pintype "passive"))
    )
    (net (code "7") (name "Net-(C10-Pad2)") (class "Default")
      (node (ref "C10") (pin "2") (pinfunction "2_2") (pintype "passive"))
      (node (ref "R26") (pin "1") (pinfunction "1_1") (pintype "passive"))
      (node (ref "R27") (pin "2") (pinfunction "2_2") (pintype "passive"))
      (node (ref "R28") (pin "1") (pinfunction "1_1") (pintype "passive"))
      (node (ref "R29") (pin "2") (pinfunction "2_2") (pintype "passive"))
      (node (ref "R35") (pin "2") (pinfunction "2_2") (pintype "passive"))
      (node (ref "R40") (pin "1") (pinfunction "1_1") (pintype "passive"))
      (node (ref "R60") (pin "2") (pinfunction "2_2") (pintype "passive"))
      (node (ref "R74") (pin "2") (pinfunction "2_2") (pintype "passive"))
    )
    (net (code "8") (name "Net-(C11-Pad2)") (class "Default")
      (node (ref "C11") (pin "2") (pinfunction "2_2") (pintype "passive"))
      (node (ref "R52") (pin "1") (pinfunction "1_1") (pintype "passive"))
      (node (ref "R53") (pin "2") (pinfunction "2_2") (pintype "passive"))
      (node (ref "R54") (pin "1") (pinfunction "1_1") (pintype "passive"))
      (node (ref "R55") (pin "2") (pinfunction "2_2") (pintype "passive"))
      (node (ref "R57") (pin "2") (pinfunction "2_2") (pintype "passive"))
      (node (ref "R61") (pin "1") (pinfunction "1_1") (pintype "passive"))
      (node (ref "R62") (pin "2") (pinfunction "2_2") (pintype "passive"))
      (node (ref "R75") (pin "2") (pinfunction "2_2") (pintype "passive"))
    )
    (net (code "9") (name "Net-(C27-Pad+)") (class "Default")
      (node (ref "C27") (pin "+") (pinfunction "+_+") (pintype "passive"))
      (node (ref "R74") (pin "1") (pinfunction "1_1") (pintype "passive"))
    )
    (net (code "10") (name "Net-(C27-Pad-)") (class "Default")
      (node (ref "C27") (pin "-") (pinfunction "-_-") (pintype "passive"))
      (node (ref "U$2") (pin "R") (pinfunction "R_R") (pintype "bidirectional"))
    )
    (net (code "11") (name "Net-(C28-Pad+)") (class "Default")
      (node (ref "C28") (pin "+") (pinfunction "+_+") (pintype "passive"))
      (node (ref "R75") (pin "1") (pinfunction "1_1") (pintype "passive"))
    )
    (net (code "12") (name "Net-(C28-Pad-)") (class "Default")
      (node (ref "C28") (pin "-") (pinfunction "-_-") (pintype "passive"))
      (node (ref "U$2") (pin "L") (pinfunction "L_L") (pintype "bidirectional"))
    )
    (net (code "13") (name "Net-(CN1-2)") (class "Default")
      (node (ref "C12") (pin "1") (pinfunction "1_1") (pintype "passive"))
      (node (ref "CN1") (pin "1") (pinfunction "2_1") (pintype "passive"))
      (node (ref "R9") (pin "2") (pinfunction "2_2") (pintype "passive"))
      (node (ref "S1") (pin "2") (pinfunction "P_2") (pintype "passive"))
      (node (ref "U3") (pin "6") (pinfunction "6_VOUT_6") (pintype "bidirectional"))
    )
    (net (code "14") (name "Net-(D3-PadC)") (class "Default")
      (node (ref "D3") (pin "C") (pinfunction "C_C") (pintype "passive"))
      (node (ref "D4") (pin "C") (pinfunction "C_C") (pintype "passive"))
    )
    (net (code "15") (name "Net-(D7-PadC)") (class "Default")
      (node (ref "D7") (pin "C") (pinfunction "C_C") (pintype "passive"))
      (node (ref "D8") (pin "C") (pinfunction "C_C") (pintype "passive"))
    )
    (net (code "16") (name "Net-(JP1-VCC)") (class "Default")
      (node (ref "C5") (pin "1") (pinfunction "1_1") (pintype "passive"))
      (node (ref "JP1") (pin "1") (pinfunction "VCC_1") (pintype "bidirectional"))
      (node (ref "U3") (pin "1") (pinfunction "1_VIN_1") (pintype "bidirectional"))
    )
    (net (code "17") (name "Net-(LED1-PadC)") (class "Default")
      (node (ref "LED1") (pin "C") (pinfunction "C_C") (pintype "passive"))
      (node (ref "Q11") (pin "B") (pinfunction "B_B") (pintype "passive"))
      (node (ref "R11") (pin "2") (pinfunction "2_2") (pintype "passive"))
    )
    (net (code "18") (name "Net-(LED2-PadA)") (class "Default")
      (node (ref "LED2") (pin "A") (pinfunction "A_A") (pintype "passive"))
      (node (ref "Q5") (pin "B") (pinfunction "B_B") (pintype "passive"))
      (node (ref "R20") (pin "1") (pinfunction "1_1") (pintype "passive"))
    )
    (net (code "19") (name "Net-(LED3-PadC)") (class "Default")
      (node (ref "LED3") (pin "C") (pinfunction "C_C") (pintype "passive"))
      (node (ref "Q9") (pin "B") (pinfunction "B_B") (pintype "passive"))
      (node (ref "R30") (pin "2") (pinfunction "2_2") (pintype "passive"))
    )
    (net (code "20") (name "Net-(LED4-PadA)") (class "Default")
      (node (ref "LED4") (pin "A") (pinfunction "A_A") (pintype "passive"))
      (node (ref "Q18") (pin "B") (pinfunction "B_B") (pintype "passive"))
      (node (ref "R46") (pin "1") (pinfunction "1_1") (pintype "passive"))
    )
    (net (code "21") (name "Net-(LED5-C)") (class "Default")
      (node (ref "LED5") (pin "K") (pinfunction "C_K") (pintype "passive"))
      (node (ref "U3") (pin "4") (pinfunction "4_CHG_4") (pintype "bidirectional"))
    )
    (net (code "22") (name "Net-(LED5-PadA)") (class "Default")
      (node (ref "LED5") (pin "A") (pinfunction "A_A") (pintype "passive"))
      (node (ref "R9") (pin "1") (pinfunction "1_1") (pintype "passive"))
    )
    (net (code "23") (name "Net-(LED6-PadA)") (class "Default")
      (node (ref "LED6") (pin "A") (pinfunction "A_A") (pintype "passive"))
      (node (ref "R73") (pin "1") (pinfunction "1_1") (pintype "passive"))
    )
    (net (code "24") (name "Net-(Q1-D)") (class "Default")
      (node (ref "Q1") (pin "1") (pinfunction "D_1") (pintype "passive"))
      (node (ref "R10") (pin "1") (pinfunction "1_1") (pintype "passive"))
    )
    (net (code "25") (name "Net-(Q1-G)") (class "Default")
      (node (ref "C10") (pin "1") (pinfunction "1_1") (pintype "passive"))
      (node (ref "Q1") (pin "3") (pinfunction "G_3") (pintype "passive"))
      (node (ref "Q3") (pin "3") (pinfunction "G_3") (pintype "passive"))
      (node (ref "R34") (pin "2") (pinfunction "2_2") (pintype "passive"))
      (node (ref "R35") (pin "1") (pinfunction "1_1") (pintype "passive"))
    )
    (net (code "26") (name "Net-(Q1-S)") (class "Default")
      (node (ref "Q1") (pin "2") (pinfunction "S_2") (pintype "passive"))
      (node (ref "R13") (pin "2") (pinfunction "2_2") (pintype "passive"))
    )
    (net (code "27") (name "Net-(Q2-D)") (class "Default")
      (node (ref "Q2") (pin "1") (pinfunction "D_1") (pintype "passive"))
      (node (ref "Q6") (pin "B") (pinfunction "B_B") (pintype "passive"))
      (node (ref "R14") (pin "2") (pinfunction "2_2") (pintype "passive"))
    )
    (net (code "28") (name "Net-(Q2-G)") (class "Default")
      (node (ref "Q2") (pin "3") (pinfunction "G_3") (pintype "passive"))
      (node (ref "Q4") (pin "3") (pinfunction "G_3") (pintype "passive"))
      (node (ref "U$4") (pin "O2") (pinfunction "2_O2") (pintype "passive"))
    )
    (net (code "29") (name "Net-(Q2-S)") (class "Default")
      (node (ref "Q2") (pin "2") (pinfunction "S_2") (pintype "passive"))
      (node (ref "R12") (pin "1") (pinfunction "1_1") (pintype "passive"))
    )
    (net (code "30") (name "Net-(Q3-D)") (class "Default")
      (node (ref "Q3") (pin "1") (pinfunction "D_1") (pintype "passive"))
      (node (ref "R15") (pin "1") (pinfunction "1_1") (pintype "passive"))
    )
    (net (code "31") (name "Net-(Q3-S)") (class "Default")
      (node (ref "Q3") (pin "2") (pinfunction "S_2") (pintype "passive"))
      (node (ref "R17") (pin "2") (pinfunction "2_2") (pintype "passive"))
    )
    (net (code "32") (name "Net-(Q4-D)") (class "Default")
      (node (ref "Q4") (pin "1") (pinfunction "D_1") (pintype "passive"))
      (node (ref "R18") (pin "2") (pinfunction "2_2") (pintype "passive"))
    )
    (net (code "33") (name "Net-(Q4-S)") (class "Default")
      (node (ref "Q12") (pin "B") (pinfunction "B_B") (pintype "passive"))
      (node (ref "Q4") (pin "2") (pinfunction "S_2") (pintype "passive"))
      (node (ref "R16") (pin "1") (pinfunction "1_1") (pintype "passive"))
    )
    (net (code "34") (name "Net-(Q5-PadC)") (class "Default")
      (node (ref "Q5") (pin "C") (pinfunction "C_C") (pintype "passive"))
      (node (ref "R17") (pin "1") (pinfunction "1_1") (pintype "passive"))
      (node (ref "R18") (pin "1") (pinfunction "1_1") (pintype "passive"))
    )
    (net (code "35") (name "Net-(Q5-PadE)") (class "Default")
      (node (ref "Q5") (pin "E") (pinfunction "E_E") (pintype "passive"))
      (node (ref "R19") (pin "2") (pinfunction "2_2") (pintype "passive"))
    )
    (net (code "36") (name "Net-(Q6-PadE)") (class "Default")
      (node (ref "Q6") (pin "E") (pinfunction "E_E") (pintype "passive"))
      (node (ref "R22") (pin "2") (pinfunction "2_2") (pintype "passive"))
    )
    (net (code "37") (name "Net-(Q7-E)") (class "Default")
      (node (ref "Q7") (pin "3") (pinfunction "E_3") (pintype "passive"))
      (node (ref "R26") (pin "2") (pinfunction "2_2") (pintype "passive"))
    )
    (net (code "38") (name "Net-(Q8-E)") (class "Default")
      (node (ref "Q8") (pin "3") (pinfunction "E_3") (pintype "passive"))
      (node (ref "R28") (pin "2") (pinfunction "2_2") (pintype "passive"))
    )
    (net (code "39") (name "Net-(Q9-PadC)") (class "Default")
      (node (ref "Q9") (pin "C") (pinfunction "C_C") (pintype "passive"))
      (node (ref "R32") (pin "2") (pinfunction "2_2") (pintype "passive"))
      (node (ref "R33") (pin "2") (pinfunction "2_2") (pintype "passive"))
    )
    (net (code "40") (name "Net-(Q9-PadE)") (class "Default")
      (node (ref "Q9") (pin "E") (pinfunction "E_E") (pintype "passive"))
      (node (ref "R31") (pin "1") (pinfunction "1_1") (pintype "passive"))
    )
    (net (code "41") (name "Net-(Q10-D)") (class "Default")
      (node (ref "Q10") (pin "1") (pinfunction "D_1") (pintype "passive"))
      (node (ref "R32") (pin "1") (pinfunction "1_1") (pintype "passive"))
    )
    (net (code "42") (name "Net-(Q10-G)") (class "Default")
      (node (ref "C11") (pin "1") (pinfunction "1_1") (pintype "passive"))
      (node (ref "Q10") (pin "3") (pinfunction "G_3") (pintype "passive"))
      (node (ref "Q16") (pin "3") (pinfunction "G_3") (pintype "passive"))
      (node (ref "R56") (pin "2") (pinfunction "2_2") (pintype "passive"))
      (node (ref "R57") (pin "1") (pinfunction "1_1") (pintype "passive"))
    )
    (net (code "43") (name "Net-(Q10-S)") (class "Default")
      (node (ref "Q10") (pin "2") (pinfunction "S_2") (pintype "passive"))
      (node (ref "R38") (pin "2") (pinfunction "2_2") (pintype "passive"))
    )
    (net (code "44") (name "Net-(Q11-PadC)") (class "Default")
      (node (ref "Q11") (pin "C") (pinfunction "C_C") (pintype "passive"))
      (node (ref "R10") (pin "2") (pinfunction "2_2") (pintype "passive"))
      (node (ref "R12") (pin "2") (pinfunction "2_2") (pintype "passive"))
    )
    (net (code "45") (name "Net-(Q11-PadE)") (class "Default")
      (node (ref "Q11") (pin "E") (pinfunction "E_E") (pintype "passive"))
      (node (ref "R8") (pin "1") (pinfunction "1_1") (pintype "passive"))
    )
    (net (code "46") (name "Net-(Q12-PadE)") (class "Default")
      (node (ref "Q12") (pin "E") (pinfunction "E_E") (pintype "passive"))
      (node (ref "R21") (pin "1") (pinfunction "1_1") (pintype "passive"))
    )
    (net (code "47") (name "Net-(Q13-B)") (class "Default")
      (node (ref "Q13") (pin "1") (pinfunction "B_1") (pintype "passive"))
      (node (ref "Q14") (pin "1") (pinfunction "B_1") (pintype "passive"))
      (node (ref "Q26") (pin "1") (pinfunction "B_1") (pintype "passive"))
      (node (ref "Q6") (pin "C") (pinfunction "C_C") (pintype "passive"))
      (node (ref "R23") (pin "1") (pinfunction "1_1") (pintype "passive"))
      (node (ref "R25") (pin "1") (pinfunction "1_1") (pintype "passive"))
    )
    (net (code "48") (name "Net-(Q13-E)") (class "Default")
      (node (ref "Q13") (pin "3") (pinfunction "E_3") (pintype "passive"))
      (node (ref "R27") (pin "1") (pinfunction "1_1") (pintype "passive"))
    )
    (net (code "49") (name "Net-(Q14-E)") (class "Default")
      (node (ref "Q14") (pin "3") (pinfunction "E_3") (pintype "passive"))
      (node (ref "R29") (pin "1") (pinfunction "1_1") (pintype "passive"))
    )
    (net (code "50") (name "Net-(Q15-D)") (class "Default")
      (node (ref "Q15") (pin "1") (pinfunction "D_1") (pintype "passive"))
      (node (ref "Q20") (pin "B") (pinfunction "B_B") (pintype "passive"))
      (node (ref "R39") (pin "2") (pinfunction "2_2") (pintype "passive"))
    )
    (net (code "51") (name "Net-(Q15-G)") (class "Default")
      (node (ref "Q15") (pin "3") (pinfunction "G_3") (pintype "passive"))
      (node (ref "Q17") (pin "3") (pinfunction "G_3") (pintype "passive"))
      (node (ref "U$4") (pin "O1") (pinfunction "2_O1") (pintype "passive"))
    )
    (net (code "52") (name "Net-(Q15-S)") (class "Default")
      (node (ref "Q15") (pin "2") (pinfunction "S_2") (pintype "passive"))
      (node (ref "R33") (pin "1") (pinfunction "1_1") (pintype "passive"))
    )
    (net (code "53") (name "Net-(Q16-D)") (class "Default")
      (node (ref "Q16") (pin "1") (pinfunction "D_1") (pintype "passive"))
      (node (ref "R41") (pin "1") (pinfunction "1_1") (pintype "passive"))
    )
    (net (code "54") (name "Net-(Q16-S)") (class "Default")
      (node (ref "Q16") (pin "2") (pinfunction "S_2") (pintype "passive"))
      (node (ref "R43") (pin "2") (pinfunction "2_2") (pintype "passive"))
    )
    (net (code "55") (name "Net-(Q17-D)") (class "Default")
      (node (ref "Q17") (pin "1") (pinfunction "D_1") (pintype "passive"))
      (node (ref "R44") (pin "2") (pinfunction "2_2") (pintype "passive"))
    )
    (net (code "56") (name "Net-(Q17-S)") (class "Default")
      (node (ref "Q17") (pin "2") (pinfunction "S_2") (pintype "passive"))
      (node (ref "Q19") (pin "B") (pinfunction "B_B") (pintype "passive"))
      (node (ref "R42") (pin "1") (pinfunction "1_1") (pintype "passive"))
    )
    (net (code "57") (name "Net-(Q18-PadC)") (class "Default")
      (node (ref "Q18") (pin "C") (pinfunction "C_C") (pintype "passive"))
      (node (ref "R43") (pin "1") (pinfunction "1_1") (pintype "passive"))
      (node (ref "R44") (pin "1") (pinfunction "1_1") (pintype "passive"))
    )
    (net (code "58") (name "Net-(Q18-PadE)") (class "Default")
      (node (ref "Q18") (pin "E") (pinfunction "E_E") (pintype "passive"))
      (node (ref "R45") (pin "2") (pinfunction "2_2") (pintype "passive"))
    )
    (net (code "59") (name "Net-(Q19-PadE)") (class "Default")
      (node (ref "Q19") (pin "E") (pinfunction "E_E") (pintype "passive"))
      (node (ref "R47") (pin "1") (pinfunction "1_1") (pintype "passive"))
    )
    (net (code "60") (name "Net-(Q20-PadE)") (class "Default")
      (node (ref "Q20") (pin "E") (pinfunction "E_E") (pintype "passive"))
      (node (ref "R48") (pin "2") (pinfunction "2_2") (pintype "passive"))
    )
    (net (code "61") (name "Net-(Q21-B)") (class "Default")
      (node (ref "Q19") (pin "C") (pinfunction "C_C") (pintype "passive"))
      (node (ref "Q21") (pin "1") (pinfunction "B_1") (pintype "passive"))
      (node (ref "Q22") (pin "1") (pinfunction "B_1") (pintype "passive"))
      (node (ref "Q27") (pin "1") (pinfunction "B_1") (pintype "passive"))
      (node (ref "R49") (pin "2") (pinfunction "2_2") (pintype "passive"))
      (node (ref "R50") (pin "2") (pinfunction "2_2") (pintype "passive"))
    )
    (net (code "62") (name "Net-(Q21-E)") (class "Default")
      (node (ref "Q21") (pin "3") (pinfunction "E_3") (pintype "passive"))
      (node (ref "R52") (pin "2") (pinfunction "2_2") (pintype "passive"))
    )
    (net (code "63") (name "Net-(Q22-E)") (class "Default")
      (node (ref "Q22") (pin "3") (pinfunction "E_3") (pintype "passive"))
      (node (ref "R54") (pin "2") (pinfunction "2_2") (pintype "passive"))
    )
    (net (code "64") (name "Net-(Q23-B)") (class "Default")
      (node (ref "Q20") (pin "C") (pinfunction "C_C") (pintype "passive"))
      (node (ref "Q23") (pin "1") (pinfunction "B_1") (pintype "passive"))
      (node (ref "Q24") (pin "1") (pinfunction "B_1") (pintype "passive"))
      (node (ref "Q28") (pin "1") (pinfunction "B_1") (pintype "passive"))
      (node (ref "R49") (pin "1") (pinfunction "1_1") (pintype "passive"))
      (node (ref "R51") (pin "1") (pinfunction "1_1") (pintype "passive"))
    )
    (net (code "65") (name "Net-(Q23-E)") (class "Default")
      (node (ref "Q23") (pin "3") (pinfunction "E_3") (pintype "passive"))
      (node (ref "R53") (pin "1") (pinfunction "1_1") (pintype "passive"))
    )
    (net (code "66") (name "Net-(Q24-E)") (class "Default")
      (node (ref "Q24") (pin "3") (pinfunction "E_3") (pintype "passive"))
      (node (ref "R55") (pin "1") (pinfunction "1_1") (pintype "passive"))
    )
    (net (code "67") (name "Net-(Q25-B)") (class "Default")
      (node (ref "Q12") (pin "C") (pinfunction "C_C") (pintype "passive"))
      (node (ref "Q25") (pin "1") (pinfunction "B_1") (pintype "passive"))
      (node (ref "Q7") (pin "1") (pinfunction "B_1") (pintype "passive"))
      (node (ref "Q8") (pin "1") (pinfunction "B_1") (pintype "passive"))
      (node (ref "R23") (pin "2") (pinfunction "2_2") (pintype "passive"))
      (node (ref "R24") (pin "2") (pinfunction "2_2") (pintype "passive"))
    )
    (net (code "68") (name "Net-(Q25-E)") (class "Default")
      (node (ref "Q25") (pin "3") (pinfunction "E_3") (pintype "passive"))
      (node (ref "R40") (pin "2") (pinfunction "2_2") (pintype "passive"))
    )
    (net (code "69") (name "Net-(Q26-E)") (class "Default")
      (node (ref "Q26") (pin "3") (pinfunction "E_3") (pintype "passive"))
      (node (ref "R60") (pin "1") (pinfunction "1_1") (pintype "passive"))
    )
    (net (code "70") (name "Net-(Q27-E)") (class "Default")
      (node (ref "Q27") (pin "3") (pinfunction "E_3") (pintype "passive"))
      (node (ref "R61") (pin "2") (pinfunction "2_2") (pintype "passive"))
    )
    (net (code "71") (name "Net-(Q28-E)") (class "Default")
      (node (ref "Q28") (pin "3") (pinfunction "E_3") (pintype "passive"))
      (node (ref "R62") (pin "1") (pinfunction "1_1") (pintype "passive"))
    )
    (net (code "72") (name "Net-(R11-Pad1)") (class "Default")
      (node (ref "R11") (pin "1") (pinfunction "1_1") (pintype "passive"))
      (node (ref "R20") (pin "2") (pinfunction "2_2") (pintype "passive"))
      (node (ref "R58") (pin "1") (pinfunction "1_1") (pintype "passive"))
    )
    (net (code "73") (name "Net-(R30-Pad1)") (class "Default")
      (node (ref "R30") (pin "1") (pinfunction "1_1") (pintype "passive"))
      (node (ref "R46") (pin "2") (pinfunction "2_2") (pintype "passive"))
      (node (ref "R59") (pin "1") (pinfunction "1_1") (pintype "passive"))
    )
    (net (code "74") (name "Net-(R36-S)") (class "Default")
      (node (ref "R36") (pin "2") (pinfunction "S_2") (pintype "passive"))
      (node (ref "R58") (pin "2") (pinfunction "2_2") (pintype "passive"))
    )
    (net (code "75") (name "Net-(R37-S)") (class "Default")
      (node (ref "R37") (pin "2") (pinfunction "S_2") (pintype "passive"))
      (node (ref "R59") (pin "2") (pinfunction "2_2") (pintype "passive"))
    )
    (net (code "76") (name "Net-(S1A-S)") (class "Default")
      (node (ref "C7") (pin "1") (pinfunction "1_1") (pintype "passive"))
      (node (ref "C8") (pin "1") (pinfunction "1_1") (pintype "passive"))
      (node (ref "D3") (pin "A") (pinfunction "A_A") (pintype "passive"))
      (node (ref "D7") (pin "A") (pinfunction "A_A") (pintype "passive"))
      (node (ref "S1") (pin "3") (pinfunction "S_3") (pintype "passive"))
      (node (ref "T1") (pin "2") (pinfunction "P$2_2") (pintype "bidirectional"))
      (node (ref "T1") (pin "3") (pinfunction "P$3_3") (pintype "bidirectional"))
      (node (ref "T2") (pin "2") (pinfunction "P$2_2") (pintype "bidirectional"))
      (node (ref "T2") (pin "3") (pinfunction "P$3_3") (pintype "bidirectional"))
      (node (ref "U1") (pin "5") (pinfunction "VIN_5") (pintype "power_in"))
      (node (ref "U2") (pin "5") (pinfunction "VIN_5") (pintype "power_in"))
    )
    (net (code "77") (name "Net-(T1-P$1)") (class "Default")
      (node (ref "D2") (pin "C") (pinfunction "C_C") (pintype "passive"))
      (node (ref "T1") (pin "1") (pinfunction "P$1_1") (pintype "bidirectional"))
    )
    (net (code "78") (name "Net-(T1-P$5)") (class "Default")
      (node (ref "D1") (pin "A") (pinfunction "A_A") (pintype "passive"))
      (node (ref "T1") (pin "5") (pinfunction "P$5_5") (pintype "bidirectional"))
    )
    (net (code "79") (name "Net-(T1-P$6)") (class "Default")
      (node (ref "D4") (pin "A") (pinfunction "A_A") (pintype "passive"))
      (node (ref "T1") (pin "6") (pinfunction "P$6_6") (pintype "bidirectional"))
      (node (ref "T1") (pin "7") (pinfunction "P$7_7") (pintype "bidirectional"))
      (node (ref "U1") (pin "8") (pinfunction "VSW_8") (pintype "output"))
    )
    (net (code "80") (name "Net-(T2-P$1)") (class "Default")
      (node (ref "D6") (pin "C") (pinfunction "C_C") (pintype "passive"))
      (node (ref "T2") (pin "1") (pinfunction "P$1_1") (pintype "bidirectional"))
    )
    (net (code "81") (name "Net-(T2-P$5)") (class "Default")
      (node (ref "D5") (pin "A") (pinfunction "A_A") (pintype "passive"))
      (node (ref "T2") (pin "5") (pinfunction "P$5_5") (pintype "bidirectional"))
    )
    (net (code "82") (name "Net-(T2-P$6)") (class "Default")
      (node (ref "D8") (pin "A") (pinfunction "A_A") (pintype "passive"))
      (node (ref "T2") (pin "6") (pinfunction "P$6_6") (pintype "bidirectional"))
      (node (ref "T2") (pin "7") (pinfunction "P$7_7") (pintype "bidirectional"))
      (node (ref "U2") (pin "8") (pinfunction "VSW_8") (pintype "output"))
    )
    (net (code "83") (name "Net-(U$4A-3)") (class "Default")
      (node (ref "U$3") (pin "L") (pinfunction "L_L") (pintype "bidirectional"))
      (node (ref "U$4") (pin "I1") (pinfunction "3_I1") (pintype "passive"))
    )
    (net (code "84") (name "Net-(U$4B-3)") (class "Default")
      (node (ref "U$3") (pin "R") (pinfunction "R_R") (pintype "bidirectional"))
      (node (ref "U$4") (pin "I2") (pinfunction "3_I2") (pintype "passive"))
    )
    (net (code "85") (name "Net-(U1-FB)") (class "Default")
      (node (ref "R1") (pin "1") (pinfunction "1_1") (pintype "passive"))
      (node (ref "R2") (pin "2") (pinfunction "2_2") (pintype "passive"))
      (node (ref "U1") (pin "2") (pinfunction "FB_2") (pintype "input"))
    )
    (net (code "86") (name "Net-(U1-NFB)") (class "Default")
      (node (ref "R76") (pin "2") (pinfunction "2_2") (pintype "passive"))
      (node (ref "R77") (pin "1") (pinfunction "1_1") (pintype "passive"))
      (node (ref "U1") (pin "3") (pinfunction "NFB_3") (pintype "input"))
    )
    (net (code "87") (name "Net-(U1-VC)") (class "Default")
      (node (ref "C1") (pin "1") (pinfunction "1_1") (pintype "passive"))
      (node (ref "R5") (pin "2") (pinfunction "2_2") (pintype "passive"))
      (node (ref "U1") (pin "1") (pinfunction "VC_1") (pintype "input"))
    )
    (net (code "88") (name "Net-(U2-FB)") (class "Default")
      (node (ref "R3") (pin "1") (pinfunction "1_1") (pintype "passive"))
      (node (ref "R4") (pin "2") (pinfunction "2_2") (pintype "passive"))
      (node (ref "U2") (pin "2") (pinfunction "FB_2") (pintype "input"))
    )
    (net (code "89") (name "Net-(U2-NFB)") (class "Default")
      (node (ref "R78") (pin "1") (pinfunction "1_1") (pintype "passive"))
      (node (ref "R79") (pin "2") (pinfunction "2_2") (pintype "passive"))
      (node (ref "U2") (pin "3") (pinfunction "NFB_3") (pintype "input"))
    )
    (net (code "90") (name "Net-(U2-VC)") (class "Default")
      (node (ref "C3") (pin "1") (pinfunction "1_1") (pintype "passive"))
      (node (ref "R6") (pin "2") (pinfunction "2_2") (pintype "passive"))
      (node (ref "U2") (pin "1") (pinfunction "VC_1") (pintype "input"))
    )
    (net (code "91") (name "Net-(U3-2_ISET)") (class "Default")
      (node (ref "R7") (pin "1") (pinfunction "1_1") (pintype "passive"))
      (node (ref "U3") (pin "2") (pinfunction "2_ISET_2") (pintype "bidirectional"))
    )
    (net (code "92") (name "Net-(U3-5_TS)") (class "Default")
      (node (ref "R72") (pin "2") (pinfunction "2_2") (pintype "passive"))
      (node (ref "U3") (pin "5") (pinfunction "5_TS_5") (pintype "bidirectional"))
    )
    (net (code "93") (name "Net-(U7-EN)") (class "Default")
      (node (ref "C24") (pin "+") (pinfunction "+_+") (pintype "passive"))
      (node (ref "D1") (pin "C") (pinfunction "C_C") (pintype "passive"))
      (node (ref "R1") (pin "2") (pinfunction "2_2") (pintype "passive"))
      (node (ref "U7") (pin "5") (pinfunction "EN_5") (pintype "input"))
      (node (ref "U7") (pin "8") (pinfunction "IN_8") (pintype "power_in"))
    )
    (net (code "94") (name "Net-(U7-FB)") (class "Default")
      (node (ref "C9") (pin "1") (pinfunction "1_1") (pintype "passive"))
      (node (ref "R63") (pin "1") (pinfunction "1_1") (pintype "passive"))
      (node (ref "R64") (pin "2") (pinfunction "2_2") (pintype "passive"))
      (node (ref "U7") (pin "2") (pinfunction "FB_2") (pintype "input"))
    )
    (net (code "95") (name "Net-(U7-NR{slash}SS)") (class "Default")
      (node (ref "C6") (pin "2") (pinfunction "2_2") (pintype "passive"))
      (node (ref "U7") (pin "6") (pinfunction "NR/SS_6") (pintype "input"))
    )
    (net (code "96") (name "Net-(U8-EN)") (class "Default")
      (node (ref "C26") (pin "+") (pinfunction "+_+") (pintype "passive"))
      (node (ref "D5") (pin "C") (pinfunction "C_C") (pintype "passive"))
      (node (ref "R3") (pin "2") (pinfunction "2_2") (pintype "passive"))
      (node (ref "U8") (pin "5") (pinfunction "EN_5") (pintype "input"))
      (node (ref "U8") (pin "8") (pinfunction "IN_8") (pintype "power_in"))
    )
    (net (code "97") (name "Net-(U8-FB)") (class "Default")
      (node (ref "C14") (pin "1") (pinfunction "1_1") (pintype "passive"))
      (node (ref "R65") (pin "1") (pinfunction "1_1") (pintype "passive"))
      (node (ref "R66") (pin "2") (pinfunction "2_2") (pintype "passive"))
      (node (ref "U8") (pin "2") (pinfunction "FB_2") (pintype "input"))
    )
    (net (code "98") (name "Net-(U8-NR{slash}SS)") (class "Default")
      (node (ref "C13") (pin "2") (pinfunction "2_2") (pintype "passive"))
      (node (ref "U8") (pin "6") (pinfunction "NR/SS_6") (pintype "input"))
    )
    (net (code "99") (name "Net-(U9-EN)") (class "Default")
      (node (ref "C23") (pin "-") (pinfunction "-_-") (pintype "passive"))
      (node (ref "D2") (pin "A") (pinfunction "A_A") (pintype "passive"))
      (node (ref "R76") (pin "1") (pinfunction "1_1") (pintype "passive"))
      (node (ref "U9") (pin "5") (pinfunction "EN_5") (pintype "input"))
      (node (ref "U9") (pin "8") (pinfunction "IN_8") (pintype "power_in"))
    )
    (net (code "100") (name "Net-(U9-FB)") (class "Default")
      (node (ref "C15") (pin "1") (pinfunction "1_1") (pintype "passive"))
      (node (ref "R67") (pin "1") (pinfunction "1_1") (pintype "passive"))
      (node (ref "R68") (pin "2") (pinfunction "2_2") (pintype "passive"))
      (node (ref "U9") (pin "2") (pinfunction "FB_2") (pintype "input"))
    )
    (net (code "101") (name "Net-(U9-NR{slash}SS)") (class "Default")
      (node (ref "C16") (pin "2") (pinfunction "2_2") (pintype "passive"))
      (node (ref "U9") (pin "6") (pinfunction "NR/SS_6") (pintype "input"))
    )
    (net (code "102") (name "Net-(U10-EN)") (class "Default")
      (node (ref "C25") (pin "-") (pinfunction "-_-") (pintype "passive"))
      (node (ref "D6") (pin "A") (pinfunction "A_A") (pintype "passive"))
      (node (ref "R79") (pin "1") (pinfunction "1_1") (pintype "passive"))
      (node (ref "U10") (pin "5") (pinfunction "EN_5") (pintype "input"))
      (node (ref "U10") (pin "8") (pinfunction "IN_8") (pintype "power_in"))
    )
    (net (code "103") (name "Net-(U10-FB)") (class "Default")
      (node (ref "C21") (pin "1") (pinfunction "1_1") (pintype "passive"))
      (node (ref "R69") (pin "1") (pinfunction "1_1") (pintype "passive"))
      (node (ref "R70") (pin "2") (pinfunction "2_2") (pintype "passive"))
      (node (ref "U10") (pin "2") (pinfunction "FB_2") (pintype "input"))
    )
    (net (code "104") (name "Net-(U10-NR{slash}SS)") (class "Default")
      (node (ref "C22") (pin "2") (pinfunction "2_2") (pintype "passive"))
      (node (ref "U10") (pin "6") (pinfunction "NR/SS_6") (pintype "input"))
    )
    (net (code "105") (name "V+") (class "Default")
      (node (ref "C19") (pin "+") (pinfunction "+_+") (pintype "passive"))
      (node (ref "C30") (pin "1") (pinfunction "1_1") (pintype "passive"))
      (node (ref "C9") (pin "2") (pinfunction "2_2") (pintype "passive"))
      (node (ref "LED3") (pin "A") (pinfunction "A_A") (pintype "passive"))
      (node (ref "Q21") (pin "2") (pinfunction "C_2") (pintype "passive"))
      (node (ref "Q21") (pin "4") (pinfunction "C_4") (pintype "passive"))
      (node (ref "Q22") (pin "2") (pinfunction "C_2") (pintype "passive"))
      (node (ref "Q22") (pin "4") (pinfunction "C_4") (pintype "passive"))
      (node (ref "Q27") (pin "2") (pinfunction "C_2") (pintype "passive"))
      (node (ref "Q27") (pin "4") (pinfunction "C_4") (pintype "passive"))
      (node (ref "R31") (pin "2") (pinfunction "2_2") (pintype "passive"))
      (node (ref "R37") (pin "3") (pinfunction "E_3") (pintype "passive"))
      (node (ref "R41") (pin "2") (pinfunction "2_2") (pintype "passive"))
      (node (ref "R42") (pin "2") (pinfunction "2_2") (pintype "passive"))
      (node (ref "R47") (pin "2") (pinfunction "2_2") (pintype "passive"))
      (node (ref "R63") (pin "2") (pinfunction "2_2") (pintype "passive"))
      (node (ref "R73") (pin "2") (pinfunction "2_2") (pintype "passive"))
      (node (ref "U7") (pin "1") (pinfunction "OUT_1") (pintype "output"))
    )
    (net (code "106") (name "V-") (class "Default")
      (node (ref "C15") (pin "2") (pinfunction "2_2") (pintype "passive"))
      (node (ref "C20") (pin "-") (pinfunction "-_-") (pintype "passive"))
      (node (ref "C29") (pin "1") (pinfunction "1_1") (pintype "passive"))
      (node (ref "LED4") (pin "C") (pinfunction "C_C") (pintype "passive"))
      (node (ref "Q23") (pin "2") (pinfunction "C_2") (pintype "passive"))
      (node (ref "Q23") (pin "4") (pinfunction "C_4") (pintype "passive"))
      (node (ref "Q24") (pin "2") (pinfunction "C_2") (pintype "passive"))
      (node (ref "Q24") (pin "4") (pinfunction "C_4") (pintype "passive"))
      (node (ref "Q28") (pin "2") (pinfunction "C_2") (pintype "passive"))
      (node (ref "Q28") (pin "4") (pinfunction "C_4") (pintype "passive"))
      (node (ref "R37") (pin "1") (pinfunction "A_1") (pintype "passive"))
      (node (ref "R38") (pin "1") (pinfunction "1_1") (pintype "passive"))
      (node (ref "R39") (pin "1") (pinfunction "1_1") (pintype "passive"))
      (node (ref "R45") (pin "1") (pinfunction "1_1") (pintype "passive"))
      (node (ref "R48") (pin "1") (pinfunction "1_1") (pintype "passive"))
      (node (ref "R67") (pin "2") (pinfunction "2_2") (pintype "passive"))
      (node (ref "U9") (pin "1") (pinfunction "OUT_1") (pintype "output"))
    )
    (net (code "107") (name "unconnected-(JP1-D+-Pad3)") (class "Default")
      (node (ref "JP1") (pin "3") (pinfunction "D+_3") (pintype "bidirectional"))
    )
    (net (code "108") (name "unconnected-(JP1-D--Pad2)") (class "Default")
      (node (ref "JP1") (pin "2") (pinfunction "D-_2") (pintype "bidirectional"))
    )
    (net (code "109") (name "unconnected-(JP1-ID-Pad4)") (class "Default")
      (node (ref "JP1") (pin "4") (pinfunction "ID_4") (pintype "bidirectional"))
    )
    (net (code "110") (name "unconnected-(JP1-SHIELD-PadP$6)") (class "Default")
      (node (ref "JP1") (pin "P$6") (pinfunction "SHIELD_P$6") (pintype "bidirectional"))
    )
    (net (code "111") (name "unconnected-(S1A-O-Pad1)") (class "Default")
      (node (ref "S1") (pin "1") (pinfunction "O_1") (pintype "passive"))
    )
    (net (code "112") (name "unconnected-(U1-S{slash}S-Pad4)") (class "Default")
      (node (ref "U1") (pin "4") (pinfunction "S/S_4") (pintype "input"))
    )
    (net (code "113") (name "unconnected-(U2-S{slash}S-Pad4)") (class "Default")
      (node (ref "U2") (pin "4") (pinfunction "S/S_4") (pintype "input"))
    )
    (net (code "114") (name "unconnected-(U7-DNC-Pad7)") (class "Default")
      (node (ref "U7") (pin "7") (pinfunction "DNC_7") (pintype "no_connect"))
    )
    (net (code "115") (name "unconnected-(U7-NC-Pad3)") (class "Default")
      (node (ref "U7") (pin "3") (pinfunction "NC_3") (pintype "no_connect"))
    )
    (net (code "116") (name "unconnected-(U8-DNC-Pad7)") (class "Default")
      (node (ref "U8") (pin "7") (pinfunction "DNC_7") (pintype "no_connect"))
    )
    (net (code "117") (name "unconnected-(U8-NC-Pad3)") (class "Default")
      (node (ref "U8") (pin "3") (pinfunction "NC_3") (pintype "no_connect"))
    )
    (net (code "118") (name "unconnected-(U9-DNC-Pad7)") (class "Default")
      (node (ref "U9") (pin "7") (pinfunction "DNC_7") (pintype "no_connect"))
    )
    (net (code "119") (name "unconnected-(U9-NC-Pad3)") (class "Default")
      (node (ref "U9") (pin "3") (pinfunction "NC_3") (pintype "no_connect"))
    )
    (net (code "120") (name "unconnected-(U10-DNC-Pad7)") (class "Default")
      (node (ref "U10") (pin "7") (pinfunction "DNC_7") (pintype "no_connect"))
    )
    (net (code "121") (name "unconnected-(U10-NC-Pad3)") (class "Default")
      (node (ref "U10") (pin "3") (pinfunction "NC_3") (pintype "no_connect"))
    )
  )
)
